# Relay.net
KiCad netlist of a schematic drawn in EAGLE
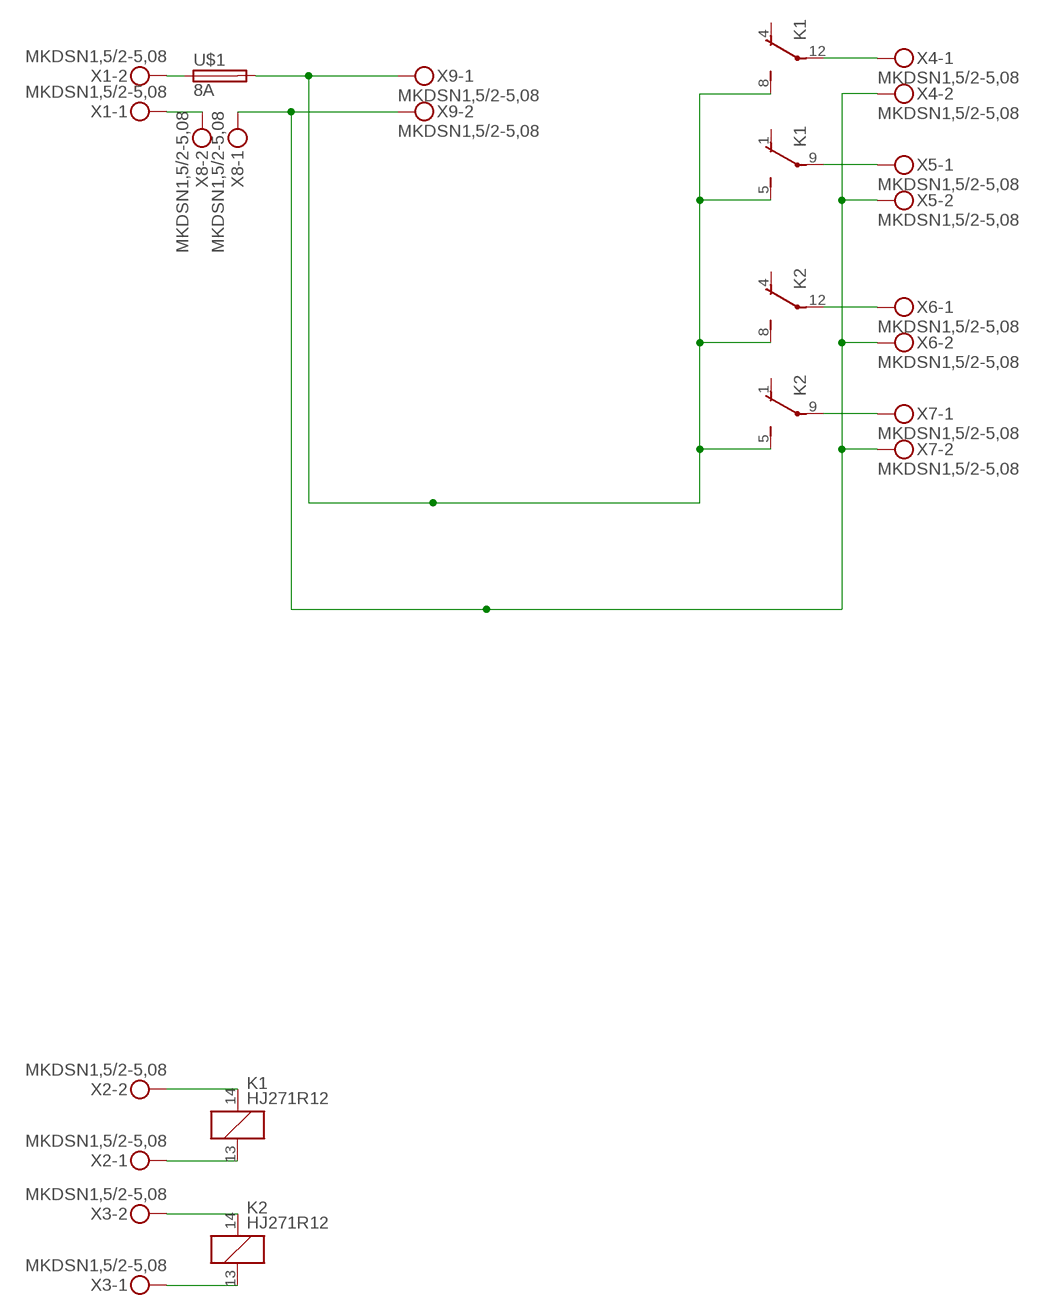
[diagram p0: schematic, sheet 1]

(export (version "E")
  (design (tool "Eeschema 10.0.6"))
  (components
    (comp (ref "K1")
      (value "HJ271R12")
      (footprint "eagle-import:PT-2")
      (libsource (lib "eagle-import") (part "HJ271R12"))
    )
    (comp (ref "K2")
      (value "HJ271R12")
      (footprint "eagle-import:PT-2")
      (libsource (lib "eagle-import") (part "HJ271R12"))
    )
    (comp (ref "U$1")
      (value "8A")
      (footprint "eagle-import:MF550")
      (libsource (lib "eagle-import") (part "MF550(マルツ)"))
    )
    (comp (ref "X1")
      (value "MKDSN1,5/2-5,08")
      (footprint "eagle-import:MKDSN1,5_2-5,08")
      (libsource (lib "eagle-import") (part "MKDSN1,5/2-5,08"))
    )
    (comp (ref "X2")
      (value "MKDSN1,5/2-5,08")
      (footprint "eagle-import:MKDSN1,5_2-5,08")
      (libsource (lib "eagle-import") (part "MKDSN1,5/2-5,08"))
    )
    (comp (ref "X3")
      (value "MKDSN1,5/2-5,08")
      (footprint "eagle-import:MKDSN1,5_2-5,08")
      (libsource (lib "eagle-import") (part "MKDSN1,5/2-5,08"))
    )
    (comp (ref "X4")
      (value "MKDSN1,5/2-5,08")
      (footprint "eagle-import:MKDSN1,5_2-5,08")
      (libsource (lib "eagle-import") (part "MKDSN1,5/2-5,08"))
    )
    (comp (ref "X5")
      (value "MKDSN1,5/2-5,08")
      (footprint "eagle-import:MKDSN1,5_2-5,08")
      (libsource (lib "eagle-import") (part "MKDSN1,5/2-5,08"))
    )
    (comp (ref "X6")
      (value "MKDSN1,5/2-5,08")
      (footprint "eagle-import:MKDSN1,5_2-5,08")
      (libsource (lib "eagle-import") (part "MKDSN1,5/2-5,08"))
    )
    (comp (ref "X7")
      (value "MKDSN1,5/2-5,08")
      (footprint "eagle-import:MKDSN1,5_2-5,08")
      (libsource (lib "eagle-import") (part "MKDSN1,5/2-5,08"))
    )
    (comp (ref "X8")
      (value "MKDSN1,5/2-5,08")
      (footprint "eagle-import:MKDSN1,5_2-5,08")
      (libsource (lib "eagle-import") (part "MKDSN1,5/2-5,08"))
    )
    (comp (ref "X9")
      (value "MKDSN1,5/2-5,08")
      (footprint "eagle-import:MKDSN1,5_2-5,08")
      (libsource (lib "eagle-import") (part "MKDSN1,5/2-5,08"))
    )
  )
  (nets
    (net (code "1") (name "Net-(K1A-1)") (class "Default")
      (node (ref "K1") (pin "14") (pinfunction "1_14") (pintype "passive"))
      (node (ref "X2") (pin "2") (pinfunction "KL_2") (pintype "passive"))
    )
    (net (code "2") (name "Net-(K1A-2)") (class "Default")
      (node (ref "K1") (pin "13") (pinfunction "2_13") (pintype "passive"))
      (node (ref "X2") (pin "1") (pinfunction "KL_1") (pintype "passive"))
    )
    (net (code "3") (name "Net-(K1B-P)") (class "Default")
      (node (ref "K1") (pin "12") (pinfunction "P_12") (pintype "passive"))
      (node (ref "X4") (pin "1") (pinfunction "KL_1") (pintype "passive"))
    )
    (net (code "4") (name "Net-(K1B-S)") (class "Default")
      (node (ref "K1") (pin "5") (pinfunction "S_5") (pintype "passive"))
      (node (ref "K1") (pin "8") (pinfunction "S_8") (pintype "passive"))
      (node (ref "K2") (pin "5") (pinfunction "S_5") (pintype "passive"))
      (node (ref "K2") (pin "8") (pinfunction "S_8") (pintype "passive"))
      (node (ref "U$1") (pin "P$2") (pinfunction "2_P$2") (pintype "passive"))
      (node (ref "X9") (pin "1") (pinfunction "KL_1") (pintype "passive"))
    )
    (net (code "5") (name "Net-(K1C-P)") (class "Default")
      (node (ref "K1") (pin "9") (pinfunction "P_9") (pintype "passive"))
      (node (ref "X5") (pin "1") (pinfunction "KL_1") (pintype "passive"))
    )
    (net (code "6") (name "Net-(K2A-1)") (class "Default")
      (node (ref "K2") (pin "14") (pinfunction "1_14") (pintype "passive"))
      (node (ref "X3") (pin "2") (pinfunction "KL_2") (pintype "passive"))
    )
    (net (code "7") (name "Net-(K2A-2)") (class "Default")
      (node (ref "K2") (pin "13") (pinfunction "2_13") (pintype "passive"))
      (node (ref "X3") (pin "1") (pinfunction "KL_1") (pintype "passive"))
    )
    (net (code "8") (name "Net-(K2B-P)") (class "Default")
      (node (ref "K2") (pin "12") (pinfunction "P_12") (pintype "passive"))
      (node (ref "X6") (pin "1") (pinfunction "KL_1") (pintype "passive"))
    )
    (net (code "9") (name "Net-(K2C-P)") (class "Default")
      (node (ref "K2") (pin "9") (pinfunction "P_9") (pintype "passive"))
      (node (ref "X7") (pin "1") (pinfunction "KL_1") (pintype "passive"))
    )
    (net (code "10") (name "Net-(U$1-1)") (class "Default")
      (node (ref "U$1") (pin "P$1") (pinfunction "1_P$1") (pintype "passive"))
      (node (ref "X1") (pin "2") (pinfunction "KL_2") (pintype "passive"))
    )
    (net (code "11") (name "Net-(X1A-KL)") (class "Default")
      (node (ref "X1") (pin "1") (pinfunction "KL_1") (pintype "passive"))
      (node (ref "X8") (pin "2") (pinfunction "KL_2") (pintype "passive"))
    )
    (net (code "12") (name "Net-(X4B-KL)") (class "Default")
      (node (ref "X4") (pin "2") (pinfunction "KL_2") (pintype "passive"))
      (node (ref "X5") (pin "2") (pinfunction "KL_2") (pintype "passive"))
      (node (ref "X6") (pin "2") (pinfunction "KL_2") (pintype "passive"))
      (node (ref "X7") (pin "2") (pinfunction "KL_2") (pintype "passive"))
      (node (ref "X8") (pin "1") (pinfunction "KL_1") (pintype "passive"))
      (node (ref "X9") (pin "2") (pinfunction "KL_2") (pintype "passive"))
    )
    (net (code "13") (name "unconnected-(K1B-O-Pad4)") (class "Default")
      (node (ref "K1") (pin "4") (pinfunction "O_4") (pintype "passive"))
    )
    (net (code "14") (name "unconnected-(K1C-O-Pad1)") (class "Default")
      (node (ref "K1") (pin "1") (pinfunction "O_1") (pintype "passive"))
    )
    (net (code "15") (name "unconnected-(K2B-O-Pad4)") (class "Default")
      (node (ref "K2") (pin "4") (pinfunction "O_4") (pintype "passive"))
    )
    (net (code "16") (name "unconnected-(K2C-O-Pad1)") (class "Default")
      (node (ref "K2") (pin "1") (pinfunction "O_1") (pintype "passive"))
    )
  )
)
